# DualPower.net
KiCad netlist of a schematic drawn in EAGLE
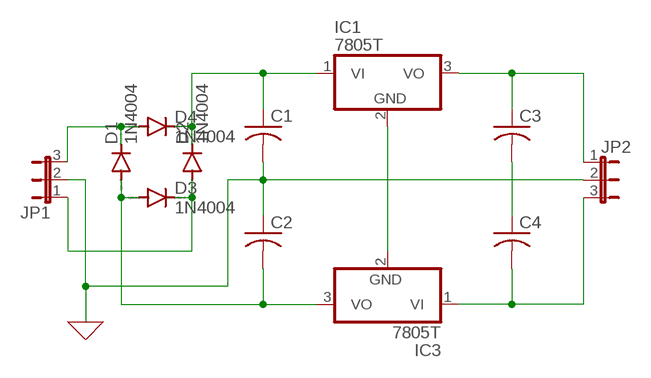
[diagram p0: schematic, sheet 1]

(export (version "E")
  (design (tool "Eeschema 10.0.6"))
  (components
    (comp (ref "C1")
      (value "C-US025-024X044")
      (footprint "eagle-import:C025-024X044")
      (libsource (lib "eagle-import") (part "C-US025-024X044"))
    )
    (comp (ref "C2")
      (value "C-US025-024X044")
      (footprint "eagle-import:C025-024X044")
      (libsource (lib "eagle-import") (part "C-US025-024X044"))
    )
    (comp (ref "C3")
      (value "C-US025-024X044")
      (footprint "eagle-import:C025-024X044")
      (libsource (lib "eagle-import") (part "C-US025-024X044"))
    )
    (comp (ref "C4")
      (value "C-US025-024X044")
      (footprint "eagle-import:C025-024X044")
      (libsource (lib "eagle-import") (part "C-US025-024X044"))
    )
    (comp (ref "D1")
      (value "1N4004")
      (footprint "eagle-import:DO41-10")
      (libsource (lib "eagle-import") (part "1N4004"))
    )
    (comp (ref "D2")
      (value "1N4004")
      (footprint "eagle-import:DO41-10")
      (libsource (lib "eagle-import") (part "1N4004"))
    )
    (comp (ref "D3")
      (value "1N4004")
      (footprint "eagle-import:DO41-10")
      (libsource (lib "eagle-import") (part "1N4004"))
    )
    (comp (ref "D4")
      (value "1N4004")
      (footprint "eagle-import:DO41-10")
      (libsource (lib "eagle-import") (part "1N4004"))
    )
    (comp (ref "IC1")
      (value "7805T")
      (footprint "eagle-import:TO220H")
      (libsource (lib "eagle-import") (part "78T05"))
    )
    (comp (ref "IC3")
      (value "7805T")
      (footprint "eagle-import:TO220H")
      (libsource (lib "eagle-import") (part "78T05"))
    )
    (comp (ref "JP1")
      (value "JP2E")
      (footprint "eagle-import:JP2")
      (libsource (lib "eagle-import") (part "JP2E"))
    )
    (comp (ref "JP2")
      (value "JP2E")
      (footprint "eagle-import:JP2")
      (libsource (lib "eagle-import") (part "JP2E"))
    )
  )
  (nets
    (net (code "1") (name "GND") (class "Default")
      (node (ref "C1") (pin "2") (pinfunction "2_2") (pintype "passive"))
      (node (ref "C2") (pin "1") (pinfunction "1_1") (pintype "passive"))
      (node (ref "JP1") (pin "2") (pinfunction "2_2") (pintype "passive"))
      (node (ref "JP2") (pin "2") (pinfunction "2_2") (pintype "passive"))
    )
    (net (code "2") (name "Net-(C3-Pad2)") (class "Default")
      (node (ref "C3") (pin "2") (pinfunction "2_2") (pintype "passive"))
      (node (ref "C4") (pin "1") (pinfunction "1_1") (pintype "passive"))
    )
    (net (code "3") (name "Net-(D1-PadC)") (class "Default")
      (node (ref "D1") (pin "C") (pinfunction "C_C") (pintype "passive"))
      (node (ref "D4") (pin "A") (pinfunction "A_A") (pintype "passive"))
      (node (ref "JP1") (pin "3") (pinfunction "3_3") (pintype "passive"))
    )
    (net (code "4") (name "Net-(D2-PadA)") (class "Default")
      (node (ref "D2") (pin "A") (pinfunction "A_A") (pintype "passive"))
      (node (ref "D3") (pin "C") (pinfunction "C_C") (pintype "passive"))
      (node (ref "JP1") (pin "1") (pinfunction "1_1") (pintype "passive"))
    )
    (net (code "5") (name "Net-(IC1-GND)") (class "Default")
      (node (ref "IC1") (pin "2") (pinfunction "GND_2") (pintype "passive"))
      (node (ref "IC3") (pin "2") (pinfunction "GND_2") (pintype "passive"))
    )
    (net (code "6") (name "Net-(IC1-VI)") (class "Default")
      (node (ref "C1") (pin "1") (pinfunction "1_1") (pintype "passive"))
      (node (ref "D2") (pin "C") (pinfunction "C_C") (pintype "passive"))
      (node (ref "D4") (pin "C") (pinfunction "C_C") (pintype "passive"))
      (node (ref "IC1") (pin "1") (pinfunction "VI_1") (pintype "input"))
    )
    (net (code "7") (name "Net-(IC1-VO)") (class "Default")
      (node (ref "C3") (pin "1") (pinfunction "1_1") (pintype "passive"))
      (node (ref "IC1") (pin "3") (pinfunction "VO_3") (pintype "passive"))
      (node (ref "JP2") (pin "1") (pinfunction "1_1") (pintype "passive"))
    )
    (net (code "8") (name "Net-(IC3-VI)") (class "Default")
      (node (ref "C4") (pin "2") (pinfunction "2_2") (pintype "passive"))
      (node (ref "IC3") (pin "1") (pinfunction "VI_1") (pintype "input"))
      (node (ref "JP2") (pin "3") (pinfunction "3_3") (pintype "passive"))
    )
    (net (code "9") (name "Net-(IC3-VO)") (class "Default")
      (node (ref "C2") (pin "2") (pinfunction "2_2") (pintype "passive"))
      (node (ref "D1") (pin "A") (pinfunction "A_A") (pintype "passive"))
      (node (ref "D3") (pin "A") (pinfunction "A_A") (pintype "passive"))
      (node (ref "IC3") (pin "3") (pinfunction "VO_3") (pintype "passive"))
    )
  )
)
